# PowerAndServo.net
KiCad netlist of a schematic drawn in Altium Designer
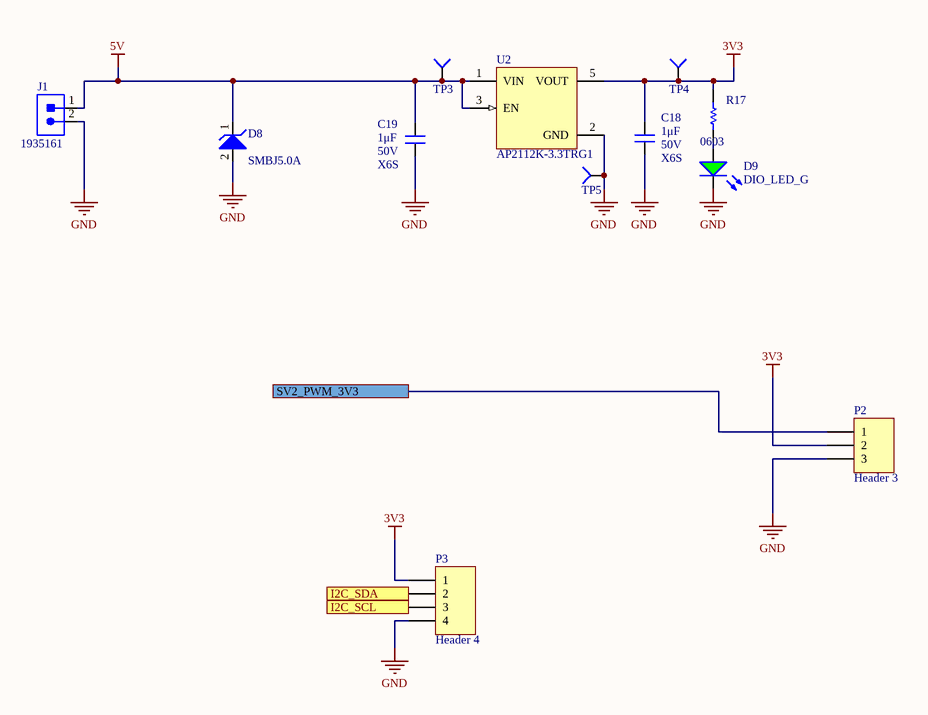
[diagram p0: PowerAndServo.SchDoc]

(export (version "E")
  (design (tool "Eeschema 10.0.6"))
  (components
    (comp (ref "C18")
      (value "1μF")
      (footprint "CAP0603")
      (description "CAP CER 1UF 50V X6S 0603")
      (fields
        (field (name "DIELECTRIC") "X6S")
        (field (name "VOLTAGE RATING") "50V")
        (field (name "Comment") "CAP_1uF_50V_0603")
      )
      (libsource (lib "UWRT_Schematic_Library_2020") (part "CAP_1uF_50V_0603"))
    )
    (comp (ref "C19")
      (value "1μF")
      (footprint "CAP0603")
      (description "CAP CER 1UF 50V X6S 0603")
      (fields
        (field (name "DIELECTRIC") "X6S")
        (field (name "VOLTAGE RATING") "50V")
        (field (name "Comment") "CAP_1uF_50V_0603")
      )
      (libsource (lib "UWRT_Schematic_Library_2020") (part "CAP_1uF_50V_0603"))
    )
    (comp (ref "D8")
      (value "TVS_DIODE_UNIDIR_5V")
      (footprint "SMBJ5.0A")
      (description "TVS DIODE 5V 9.2V SMB")
      (fields (field (name "MANUFACTURER PART NUMBER 1") "SMBJ5.0A"))
      (libsource (lib "UWRT_Schematic_Library_2020") (part "TVS_DIODE_UNIDIR_5V"))
    )
    (comp (ref "D9")
      (value "DIO_LED_G")
      (footprint "LED_0805_GREEN")
      (description "LED GREEN DIFFUSED 0805 SMD")
      (libsource (lib "UWRT_Schematic_Library_2020") (part "DIO_LED_G"))
    )
    (comp (ref "J1")
      (value "CON_2M_TERM")
      (footprint "1935161")
      (description "TERM BLK 2POS SIDE ENTRY 5MM")
      (fields (field (name "MANUFACTURER PART NUMBER 1") "1935161") (field (name "VOLTAGE") "300V"))
      (libsource (lib "UWRT_Schematic_Library_2020") (part "CON_2M_TERM"))
    )
    (comp (ref "P2")
      (value "Header 3")
      (footprint "HDR1X3")
      (description "Header, 3-Pin")
      (fields (field (name "PUBLISHER") "Altium Limited"))
      (libsource (lib "Miscellaneous Connectors") (part "Header 3"))
    )
    (comp (ref "P3")
      (value "Header 4")
      (footprint "HDR1X4")
      (description "Header, 4-Pin")
      (fields (field (name "PUBLISHER") "Altium Limited"))
      (libsource (lib "Miscellaneous Connectors") (part "Header 4"))
    )
    (comp (ref "R17")
      (value "RES_120Ω_0603_5%_HP")
      (footprint "RESC0603")
      (description "RES 120 OHM 5% 1/4W 0603")
      (fields (field (name "PACKAGE/FOOTPRINT") "0603"))
      (libsource (lib "UWRT_Schematic_Library_2020") (part "RES_120Ω_0603_5%_HP"))
    )
    (comp (ref "TP3")
      (value "TESTPOINT_SMD_LOOP")
      (footprint "S1751-46R")
      (description "TESTPOINT SMD")
      (libsource (lib "UWRT_Schematic_Library_2020") (part "TESTPOINT_SMD_LOOP"))
    )
    (comp (ref "TP4")
      (value "TESTPOINT_SMD_LOOP")
      (footprint "S1751-46R")
      (description "TESTPOINT SMD")
      (libsource (lib "UWRT_Schematic_Library_2020") (part "TESTPOINT_SMD_LOOP"))
    )
    (comp (ref "TP5")
      (value "TESTPOINT_SMD_LOOP")
      (footprint "S1751-46R")
      (description "TESTPOINT SMD")
      (libsource (lib "UWRT_Schematic_Library_2020") (part "TESTPOINT_SMD_LOOP"))
    )
    (comp (ref "U2")
      (value "LDO_3.3V_600mA")
      (footprint "SOT95P285X140-5N")
      (description "IC REG LINEAR 3.3V 600MA SOT25")
      (fields
        (field (name "MANUFACTURER PART NUMBER 1") "AP2112K-3.3TRG1")
        (field (name "LCSC PART #") "C51118")
      )
      (libsource (lib "UWRT_Schematic_Library_2020") (part "LDO_3.3V_600mA"))
    )
  )
  (nets
    (net (code "1") (name "/I2C_SCL") (class "Default")
      (node (ref "P3") (pin "3") (pinfunction "3_3") (pintype "passive"))
    )
    (net (code "2") (name "/I2C_SDA") (class "Default")
      (node (ref "P3") (pin "2") (pinfunction "2_2") (pintype "passive"))
    )
    (net (code "3") (name "/SV2_PWM_3V3") (class "Default")
      (node (ref "P2") (pin "1") (pinfunction "1_1") (pintype "passive"))
    )
    (net (code "4") (name "3V3") (class "Default")
      (node (ref "C18") (pin "2") (pinfunction "2_2") (pintype "passive"))
      (node (ref "P2") (pin "2") (pinfunction "2_2") (pintype "passive"))
      (node (ref "P3") (pin "1") (pinfunction "1_1") (pintype "passive"))
      (node (ref "R17") (pin "2") (pinfunction "2_2") (pintype "passive"))
      (node (ref "TP4") (pin "1") (pinfunction "=value_1") (pintype "passive"))
      (node (ref "U2") (pin "5") (pinfunction "VOUT_5") (pintype "power_in"))
    )
    (net (code "5") (name "5V") (class "Default")
      (node (ref "C19") (pin "2") (pinfunction "2_2") (pintype "passive"))
      (node (ref "D8") (pin "1") (pinfunction "1_1") (pintype "passive"))
      (node (ref "J1") (pin "1") (pinfunction "1_1") (pintype "passive"))
      (node (ref "TP3") (pin "1") (pinfunction "=value_1") (pintype "passive"))
      (node (ref "U2") (pin "1") (pinfunction "VIN_1") (pintype "power_in"))
      (node (ref "U2") (pin "3") (pinfunction "EN_3") (pintype "input"))
    )
    (net (code "6") (name "GND") (class "Default")
      (node (ref "C18") (pin "1") (pinfunction "1_1") (pintype "passive"))
      (node (ref "C19") (pin "1") (pinfunction "1_1") (pintype "passive"))
      (node (ref "D8") (pin "2") (pinfunction "2_2") (pintype "passive"))
      (node (ref "D9") (pin "2") (pinfunction "K_2") (pintype "passive"))
      (node (ref "J1") (pin "2") (pinfunction "2_2") (pintype "passive"))
      (node (ref "P2") (pin "3") (pinfunction "3_3") (pintype "passive"))
      (node (ref "P3") (pin "4") (pinfunction "4_4") (pintype "passive"))
      (node (ref "TP5") (pin "1") (pinfunction "=value_1") (pintype "passive"))
      (node (ref "U2") (pin "2") (pinfunction "GND_2") (pintype "power_in"))
    )
    (net (code "7") (name "Net-(D9-A)") (class "Default")
      (node (ref "D9") (pin "1") (pinfunction "A_1") (pintype "passive"))
      (node (ref "R17") (pin "1") (pinfunction "1_1") (pintype "passive"))
    )
  )
)
